# DAU_Kupplung_3phasig_V1_2.net
KiCad netlist of a schematic drawn in EAGLE
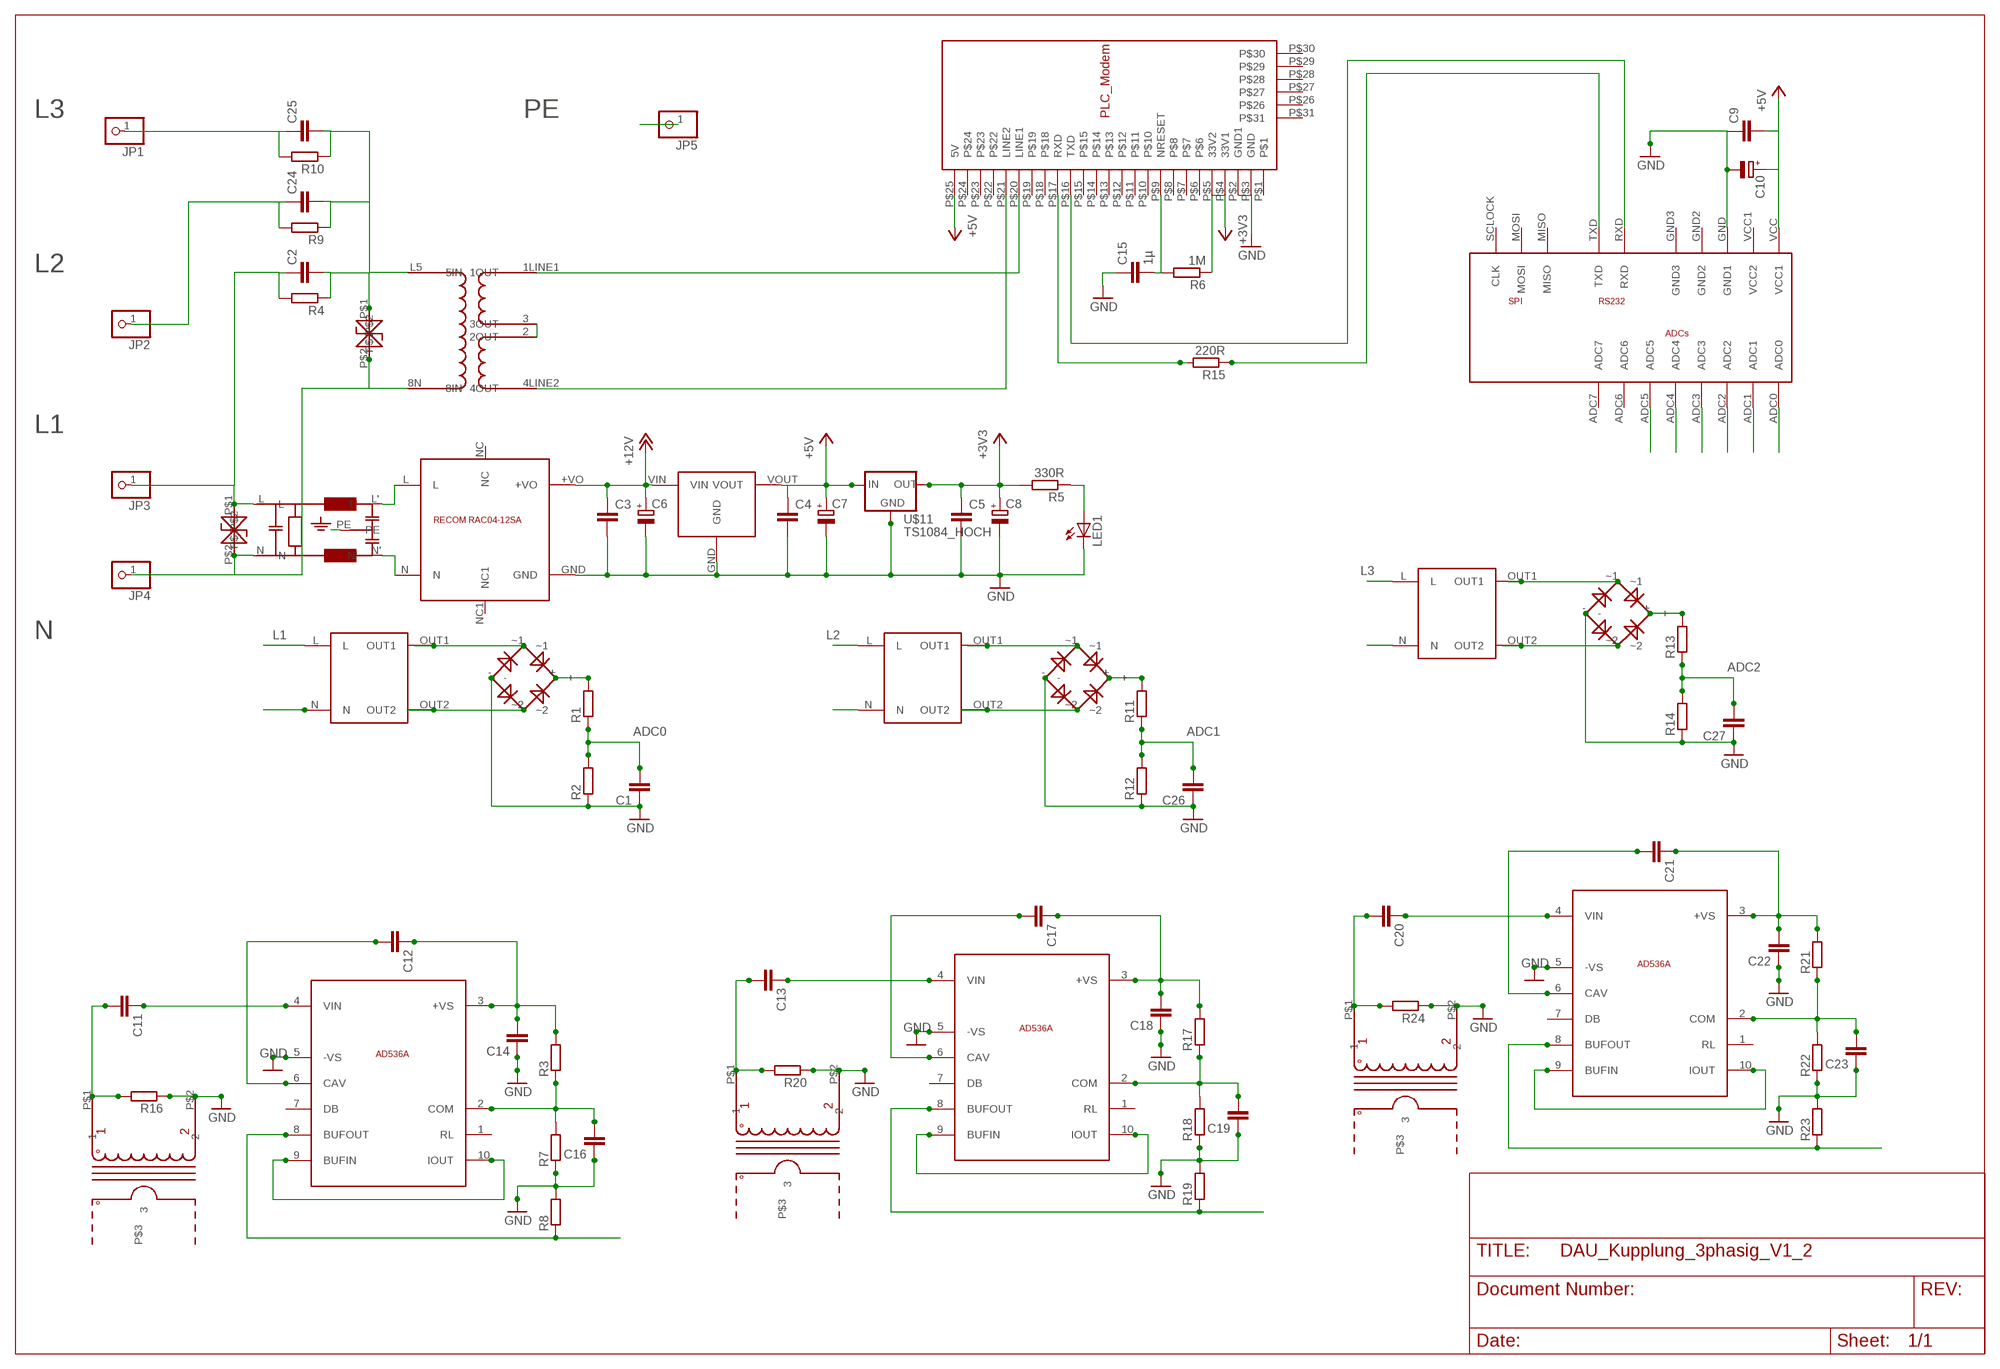
[diagram p0: schematic, sheet 1]

(export (version "E")
  (design (tool "Eeschema 10.0.6"))
  (components
    (comp (ref "C1")
      (value "C2,5-3")
      (footprint "eagle-import:C2.5-3")
      (libsource (lib "eagle-import") (part "C2,5-3"))
    )
    (comp (ref "C2")
      (value "C-EU225-087X268")
      (footprint "eagle-import:C225-087X268")
      (libsource (lib "eagle-import") (part "resistor_C-EU225-087X268"))
    )
    (comp (ref "C3")
      (value "C-EU025-040X050")
      (footprint "eagle-import:C025-040X050")
      (libsource (lib "eagle-import") (part "resistor_C-EU025-040X050"))
    )
    (comp (ref "C4")
      (value "C-EU025-040X050")
      (footprint "eagle-import:C025-040X050")
      (libsource (lib "eagle-import") (part "resistor_C-EU025-040X050"))
    )
    (comp (ref "C5")
      (value "C-EU025-040X050")
      (footprint "eagle-import:C025-040X050")
      (libsource (lib "eagle-import") (part "resistor_C-EU025-040X050"))
    )
    (comp (ref "C6")
      (value "CPOL-EUE2.5-6")
      (footprint "eagle-import:E2,5-6")
      (libsource (lib "eagle-import") (part "resistor_CPOL-EUE2.5-6"))
    )
    (comp (ref "C7")
      (value "CPOL-EUE2.5-6")
      (footprint "eagle-import:E2,5-6")
      (libsource (lib "eagle-import") (part "resistor_CPOL-EUE2.5-6"))
    )
    (comp (ref "C8")
      (value "CPOL-EUE2.5-6")
      (footprint "eagle-import:E2,5-6")
      (libsource (lib "eagle-import") (part "resistor_CPOL-EUE2.5-6"))
    )
    (comp (ref "C9")
      (value "C-EU025-040X050")
      (footprint "eagle-import:C025-040X050")
      (libsource (lib "eagle-import") (part "C-EU025-040X050"))
    )
    (comp (ref "C10")
      (value "CPOL-EUE2,5-6E")
      (footprint "eagle-import:E2,5-6E")
      (libsource (lib "eagle-import") (part "CPOL-EUE2,5-6E"))
    )
    (comp (ref "C11")
      (value "C2,5-3")
      (footprint "eagle-import:C2.5-3")
      (libsource (lib "eagle-import") (part "C2,5-3"))
    )
    (comp (ref "C12")
      (value "C2,5-3")
      (footprint "eagle-import:C2.5-3")
      (libsource (lib "eagle-import") (part "C2,5-3"))
    )
    (comp (ref "C13")
      (value "C2,5-3")
      (footprint "eagle-import:C2.5-3")
      (libsource (lib "eagle-import") (part "C2,5-3"))
    )
    (comp (ref "C14")
      (value "C2,5-3")
      (footprint "eagle-import:C2.5-3")
      (libsource (lib "eagle-import") (part "C2,5-3"))
    )
    (comp (ref "C15")
      (value "1µ")
      (footprint "eagle-import:C025-040X050")
      (libsource (lib "eagle-import") (part "resistor_C-EU025-040X050"))
    )
    (comp (ref "C16")
      (value "C2,5-3")
      (footprint "eagle-import:C2.5-3")
      (libsource (lib "eagle-import") (part "C2,5-3"))
    )
    (comp (ref "C17")
      (value "C2,5-3")
      (footprint "eagle-import:C2.5-3")
      (libsource (lib "eagle-import") (part "C2,5-3"))
    )
    (comp (ref "C18")
      (value "C2,5-3")
      (footprint "eagle-import:C2.5-3")
      (libsource (lib "eagle-import") (part "C2,5-3"))
    )
    (comp (ref "C19")
      (value "C2,5-3")
      (footprint "eagle-import:C2.5-3")
      (libsource (lib "eagle-import") (part "C2,5-3"))
    )
    (comp (ref "C20")
      (value "C2,5-3")
      (footprint "eagle-import:C2.5-3")
      (libsource (lib "eagle-import") (part "C2,5-3"))
    )
    (comp (ref "C21")
      (value "C2,5-3")
      (footprint "eagle-import:C2.5-3")
      (libsource (lib "eagle-import") (part "C2,5-3"))
    )
    (comp (ref "C22")
      (value "C2,5-3")
      (footprint "eagle-import:C2.5-3")
      (libsource (lib "eagle-import") (part "C2,5-3"))
    )
    (comp (ref "C23")
      (value "C2,5-3")
      (footprint "eagle-import:C2.5-3")
      (libsource (lib "eagle-import") (part "C2,5-3"))
    )
    (comp (ref "C24")
      (value "C-EU225-087X268")
      (footprint "eagle-import:C225-087X268")
      (libsource (lib "eagle-import") (part "resistor_C-EU225-087X268"))
    )
    (comp (ref "C25")
      (value "C-EU225-087X268")
      (footprint "eagle-import:C225-087X268")
      (libsource (lib "eagle-import") (part "resistor_C-EU225-087X268"))
    )
    (comp (ref "C26")
      (value "C2,5-3")
      (footprint "eagle-import:C2.5-3")
      (libsource (lib "eagle-import") (part "C2,5-3"))
    )
    (comp (ref "C27")
      (value "C2,5-3")
      (footprint "eagle-import:C2.5-3")
      (libsource (lib "eagle-import") (part "C2,5-3"))
    )
    (comp (ref "JP1")
      (value "PINHD-1X1")
      (footprint "eagle-import:1X01")
      (libsource (lib "eagle-import") (part "PINHD-1X1"))
    )
    (comp (ref "JP2")
      (value "PINHD-1X1")
      (footprint "eagle-import:1X01")
      (libsource (lib "eagle-import") (part "PINHD-1X1"))
    )
    (comp (ref "JP3")
      (value "PINHD-1X1")
      (footprint "eagle-import:1X01")
      (libsource (lib "eagle-import") (part "PINHD-1X1"))
    )
    (comp (ref "JP4")
      (value "PINHD-1X1")
      (footprint "eagle-import:1X01")
      (libsource (lib "eagle-import") (part "PINHD-1X1"))
    )
    (comp (ref "JP5")
      (value "PINHD-1X1")
      (footprint "eagle-import:1X01")
      (libsource (lib "eagle-import") (part "PINHD-1X1"))
    )
    (comp (ref "LED1")
      (value "LEDSQR2X5")
      (footprint "eagle-import:LED2X5")
      (libsource (lib "eagle-import") (part "LEDSQR2X5"))
    )
    (comp (ref "R1")
      (value "R-EU_0204/7")
      (footprint "eagle-import:0204_7")
      (libsource (lib "eagle-import") (part "R-EU_0204/7"))
    )
    (comp (ref "R2")
      (value "R-EU_0204/7")
      (footprint "eagle-import:0204_7")
      (libsource (lib "eagle-import") (part "R-EU_0204/7"))
    )
    (comp (ref "R3")
      (value "R-EU_0204/7")
      (footprint "eagle-import:0204_7")
      (libsource (lib "eagle-import") (part "R-EU_0204/7"))
    )
    (comp (ref "R4")
      (value "R-EU_0204/7")
      (footprint "eagle-import:0204_7")
      (libsource (lib "eagle-import") (part "R-EU_0204/7"))
    )
    (comp (ref "R5")
      (value "330R")
      (footprint "eagle-import:0204_7")
      (libsource (lib "eagle-import") (part "R-EU_0204/7"))
    )
    (comp (ref "R6")
      (value "1M")
      (footprint "eagle-import:0204_7")
      (libsource (lib "eagle-import") (part "R-EU_0204/7"))
    )
    (comp (ref "R7")
      (value "R-EU_0204/7")
      (footprint "eagle-import:0204_7")
      (libsource (lib "eagle-import") (part "R-EU_0204/7"))
    )
    (comp (ref "R8")
      (value "R-EU_0204/7")
      (footprint "eagle-import:0204_7")
      (libsource (lib "eagle-import") (part "R-EU_0204/7"))
    )
    (comp (ref "R9")
      (value "R-EU_0204/7")
      (footprint "eagle-import:0204_7")
      (libsource (lib "eagle-import") (part "R-EU_0204/7"))
    )
    (comp (ref "R10")
      (value "R-EU_0204/7")
      (footprint "eagle-import:0204_7")
      (libsource (lib "eagle-import") (part "R-EU_0204/7"))
    )
    (comp (ref "R11")
      (value "R-EU_0204/7")
      (footprint "eagle-import:0204_7")
      (libsource (lib "eagle-import") (part "R-EU_0204/7"))
    )
    (comp (ref "R12")
      (value "R-EU_0204/7")
      (footprint "eagle-import:0204_7")
      (libsource (lib "eagle-import") (part "R-EU_0204/7"))
    )
    (comp (ref "R13")
      (value "R-EU_0204/7")
      (footprint "eagle-import:0204_7")
      (libsource (lib "eagle-import") (part "R-EU_0204/7"))
    )
    (comp (ref "R14")
      (value "R-EU_0204/7")
      (footprint "eagle-import:0204_7")
      (libsource (lib "eagle-import") (part "R-EU_0204/7"))
    )
    (comp (ref "R15")
      (value "220R")
      (footprint "eagle-import:0204_7")
      (libsource (lib "eagle-import") (part "R-EU_0204/7"))
    )
    (comp (ref "R16")
      (value "R-EU_0204/7")
      (footprint "eagle-import:0204_7")
      (libsource (lib "eagle-import") (part "R-EU_0204/7"))
    )
    (comp (ref "R17")
      (value "R-EU_0204/7")
      (footprint "eagle-import:0204_7")
      (libsource (lib "eagle-import") (part "R-EU_0204/7"))
    )
    (comp (ref "R18")
      (value "R-EU_0204/7")
      (footprint "eagle-import:0204_7")
      (libsource (lib "eagle-import") (part "R-EU_0204/7"))
    )
    (comp (ref "R19")
      (value "R-EU_0204/7")
      (footprint "eagle-import:0204_7")
      (libsource (lib "eagle-import") (part "R-EU_0204/7"))
    )
    (comp (ref "R20")
      (value "R-EU_0204/7")
      (footprint "eagle-import:0204_7")
      (libsource (lib "eagle-import") (part "R-EU_0204/7"))
    )
    (comp (ref "R21")
      (value "R-EU_0204/7")
      (footprint "eagle-import:0204_7")
      (libsource (lib "eagle-import") (part "R-EU_0204/7"))
    )
    (comp (ref "R22")
      (value "R-EU_0204/7")
      (footprint "eagle-import:0204_7")
      (libsource (lib "eagle-import") (part "R-EU_0204/7"))
    )
    (comp (ref "R23")
      (value "R-EU_0204/7")
      (footprint "eagle-import:0204_7")
      (libsource (lib "eagle-import") (part "R-EU_0204/7"))
    )
    (comp (ref "R24")
      (value "R-EU_0204/7")
      (footprint "eagle-import:0204_7")
      (libsource (lib "eagle-import") (part "R-EU_0204/7"))
    )
    (comp (ref "TSV1")
      (value "TSV")
      (footprint "eagle-import:TSV")
      (libsource (lib "eagle-import") (part "TSV"))
    )
    (comp (ref "TSV2")
      (value "TSV")
      (footprint "eagle-import:TSV")
      (libsource (lib "eagle-import") (part "TSV"))
    )
    (comp (ref "U$1")
      (value "RECOM_RAC04_12SA")
      (footprint "eagle-import:RAC04_12SA")
      (libsource (lib "eagle-import") (part "RECOM_RAC04_12SA"))
    )
    (comp (ref "U$2")
      (value "SICHERHEITSTRAFO")
      (footprint "eagle-import:TRAFO_0,35VA")
      (libsource (lib "eagle-import") (part "SICHERHEITSTRAFO"))
    )
    (comp (ref "U$3")
      (value "ADUC831_MINIMUM")
      (footprint "eagle-import:ADUC_MINIMUM")
      (libsource (lib "eagle-import") (part "ADUC831_MINIMUM"))
    )
    (comp (ref "U$4")
      (value "MODEMSTECKER")
      (footprint "eagle-import:MODEM_FUSS")
      (libsource (lib "eagle-import") (part "MODEMSTECKER"))
    )
    (comp (ref "U$5")
      (value "PLC_UEBERTRAGER_V2")
      (footprint "eagle-import:PLC-UEBERTRAGER_V2")
      (libsource (lib "eagle-import") (part "PLC_UEBERTRAGER_V2"))
    )
    (comp (ref "U$6")
      (value "AC1010")
      (footprint "eagle-import:AC1010")
      (libsource (lib "eagle-import") (part "AC1010"))
    )
    (comp (ref "U$7")
      (value "AC1010")
      (footprint "eagle-import:AC1010")
      (libsource (lib "eagle-import") (part "AC1010"))
    )
    (comp (ref "U$8")
      (value "RECTIFIER")
      (footprint "eagle-import:RECTIFIER")
      (libsource (lib "eagle-import") (part "RECTIFIER"))
    )
    (comp (ref "U$10")
      (value "RECOM_785_05")
      (footprint "eagle-import:RECOM785X")
      (libsource (lib "eagle-import") (part "RECOM_785_05"))
    )
    (comp (ref "U$11")
      (value "TS1084_HOCH")
      (footprint "eagle-import:TS1084_HOCH")
      (libsource (lib "eagle-import") (part "TS1084_HOCH"))
    )
    (comp (ref "U$12")
      (value "AD536")
      (footprint "eagle-import:TO100_10PIN")
      (libsource (lib "eagle-import") (part "AD536"))
    )
    (comp (ref "U$13")
      (value "AD536")
      (footprint "eagle-import:TO100_10PIN")
      (libsource (lib "eagle-import") (part "AD536"))
    )
    (comp (ref "U$14")
      (value "AC1010")
      (footprint "eagle-import:AC1010")
      (libsource (lib "eagle-import") (part "AC1010"))
    )
    (comp (ref "U$15")
      (value "AD536")
      (footprint "eagle-import:TO100_10PIN")
      (libsource (lib "eagle-import") (part "AD536"))
    )
    (comp (ref "U$16")
      (value "SICHERHEITSTRAFO")
      (footprint "eagle-import:TRAFO_0,35VA")
      (libsource (lib "eagle-import") (part "SICHERHEITSTRAFO"))
    )
    (comp (ref "U$17")
      (value "RECTIFIER")
      (footprint "eagle-import:RECTIFIER")
      (libsource (lib "eagle-import") (part "RECTIFIER"))
    )
    (comp (ref "U$18")
      (value "SICHERHEITSTRAFO")
      (footprint "eagle-import:TRAFO_0,35VA")
      (libsource (lib "eagle-import") (part "SICHERHEITSTRAFO"))
    )
    (comp (ref "U$19")
      (value "RECTIFIER")
      (footprint "eagle-import:RECTIFIER")
      (libsource (lib "eagle-import") (part "RECTIFIER"))
    )
    (comp (ref "U$20")
      (value "NETZFILTER_05_A")
      (footprint "eagle-import:NETZFILTER")
      (libsource (lib "eagle-import") (part "NETZFILTER_05_A"))
    )
  )
  (nets
    (net (code "1") (name "+3V3") (class "Default")
      (node (ref "C5") (pin "1") (pinfunction "1_1") (pintype "passive"))
      (node (ref "C8") (pin "+") (pinfunction "+_+") (pintype "passive"))
      (node (ref "R5") (pin "2") (pinfunction "2_2") (pintype "passive"))
      (node (ref "R6") (pin "1") (pinfunction "1_1") (pintype "passive"))
      (node (ref "U$11") (pin "OUT") (pinfunction "OUT_OUT") (pintype "passive"))
      (node (ref "U$4") (pin "P$4") (pinfunction "33V1_P$4") (pintype "bidirectional"))
      (node (ref "U$4") (pin "P$5") (pinfunction "33V2_P$5") (pintype "bidirectional"))
    )
    (net (code "2") (name "+5V") (class "Default")
      (node (ref "C10") (pin "+") (pinfunction "+_+") (pintype "passive"))
      (node (ref "C4") (pin "1") (pinfunction "1_1") (pintype "passive"))
      (node (ref "C7") (pin "+") (pinfunction "+_+") (pintype "passive"))
      (node (ref "C9") (pin "2") (pinfunction "2_2") (pintype "passive"))
      (node (ref "U$10") (pin "VOUT") (pinfunction "VOUT_VOUT") (pintype "bidirectional"))
      (node (ref "U$11") (pin "IN") (pinfunction "IN_IN") (pintype "input"))
      (node (ref "U$3") (pin "VCC") (pinfunction "VCC1_VCC") (pintype "bidirectional"))
      (node (ref "U$4") (pin "P$25") (pinfunction "5V_P$25") (pintype "bidirectional"))
    )
    (net (code "3") (name "+12V") (class "Default")
      (node (ref "C3") (pin "1") (pinfunction "1_1") (pintype "passive"))
      (node (ref "C6") (pin "+") (pinfunction "+_+") (pintype "passive"))
      (node (ref "U$1") (pin "+VO") (pinfunction "+VO_+VO") (pintype "bidirectional"))
      (node (ref "U$10") (pin "VIN") (pinfunction "VIN_VIN") (pintype "bidirectional"))
    )
    (net (code "4") (name "/ADC0") (class "Default")
      (node (ref "C1") (pin "2") (pinfunction "2_2") (pintype "passive"))
      (node (ref "R1") (pin "1") (pinfunction "1_1") (pintype "passive"))
      (node (ref "R2") (pin "2") (pinfunction "2_2") (pintype "passive"))
      (node (ref "U$3") (pin "ADC0") (pinfunction "ADC0_ADC0") (pintype "bidirectional"))
    )
    (net (code "5") (name "/ADC1") (class "Default")
      (node (ref "C26") (pin "2") (pinfunction "2_2") (pintype "passive"))
      (node (ref "R11") (pin "1") (pinfunction "1_1") (pintype "passive"))
      (node (ref "R12") (pin "2") (pinfunction "2_2") (pintype "passive"))
      (node (ref "U$3") (pin "ADC1") (pinfunction "ADC1_ADC1") (pintype "bidirectional"))
    )
    (net (code "6") (name "/ADC2") (class "Default")
      (node (ref "C27") (pin "2") (pinfunction "2_2") (pintype "passive"))
      (node (ref "R13") (pin "1") (pinfunction "1_1") (pintype "passive"))
      (node (ref "R14") (pin "2") (pinfunction "2_2") (pintype "passive"))
      (node (ref "U$3") (pin "ADC2") (pinfunction "ADC2_ADC2") (pintype "bidirectional"))
    )
    (net (code "7") (name "/ADC3") (class "Default")
      (node (ref "R8") (pin "1") (pinfunction "1_1") (pintype "passive"))
      (node (ref "U$13") (pin "8") (pinfunction "BUFOUT_8") (pintype "bidirectional"))
      (node (ref "U$3") (pin "ADC3") (pinfunction "ADC3_ADC3") (pintype "bidirectional"))
    )
    (net (code "8") (name "/ADC4") (class "Default")
      (node (ref "R19") (pin "1") (pinfunction "1_1") (pintype "passive"))
      (node (ref "U$12") (pin "8") (pinfunction "BUFOUT_8") (pintype "bidirectional"))
      (node (ref "U$3") (pin "ADC4") (pinfunction "ADC4_ADC4") (pintype "bidirectional"))
    )
    (net (code "9") (name "/ADC5") (class "Default")
      (node (ref "R23") (pin "1") (pinfunction "1_1") (pintype "passive"))
      (node (ref "U$15") (pin "8") (pinfunction "BUFOUT_8") (pintype "bidirectional"))
      (node (ref "U$3") (pin "ADC5") (pinfunction "ADC5_ADC5") (pintype "bidirectional"))
    )
    (net (code "10") (name "/L1") (class "Default")
      (node (ref "C2") (pin "1") (pinfunction "1_1") (pintype "passive"))
      (node (ref "JP3") (pin "1") (pinfunction "1_1") (pintype "passive"))
      (node (ref "R4") (pin "2") (pinfunction "2_2") (pintype "passive"))
      (node (ref "TSV1") (pin "P$1") (pinfunction "P$1_P$1") (pintype "bidirectional"))
      (node (ref "U$2") (pin "L") (pinfunction "L_L") (pintype "bidirectional"))
      (node (ref "U$20") (pin "L") (pinfunction "L_L") (pintype "bidirectional"))
    )
    (net (code "11") (name "/L2") (class "Default")
      (node (ref "C24") (pin "1") (pinfunction "1_1") (pintype "passive"))
      (node (ref "JP2") (pin "1") (pinfunction "1_1") (pintype "passive"))
      (node (ref "R9") (pin "2") (pinfunction "2_2") (pintype "passive"))
      (node (ref "U$16") (pin "L") (pinfunction "L_L") (pintype "bidirectional"))
    )
    (net (code "12") (name "/L3") (class "Default")
      (node (ref "C25") (pin "1") (pinfunction "1_1") (pintype "passive"))
      (node (ref "JP1") (pin "1") (pinfunction "1_1") (pintype "passive"))
      (node (ref "R10") (pin "2") (pinfunction "2_2") (pintype "passive"))
      (node (ref "U$18") (pin "L") (pinfunction "L_L") (pintype "bidirectional"))
    )
    (net (code "13") (name "/N") (class "Default")
      (node (ref "JP4") (pin "1") (pinfunction "1_1") (pintype "passive"))
      (node (ref "TSV1") (pin "P$2") (pinfunction "P$2_P$2") (pintype "bidirectional"))
      (node (ref "TSV2") (pin "P$2") (pinfunction "P$2_P$2") (pintype "bidirectional"))
      (node (ref "U$16") (pin "N") (pinfunction "N_N") (pintype "bidirectional"))
      (node (ref "U$18") (pin "N") (pinfunction "N_N") (pintype "bidirectional"))
      (node (ref "U$2") (pin "N") (pinfunction "N_N") (pintype "bidirectional"))
      (node (ref "U$20") (pin "N") (pinfunction "N_N") (pintype "bidirectional"))
      (node (ref "U$5") (pin "8N") (pinfunction "8IN_8N") (pintype "input"))
    )
    (net (code "14") (name "/PE") (class "Default")
      (node (ref "JP5") (pin "1") (pinfunction "1_1") (pintype "passive"))
      (node (ref "U$20") (pin "PE") (pinfunction "PE_PE") (pintype "input"))
    )
    (net (code "15") (name "GND") (class "Default")
      (node (ref "C1") (pin "1") (pinfunction "1_1") (pintype "passive"))
      (node (ref "C10") (pin "-") (pinfunction "-_-") (pintype "passive"))
      (node (ref "C14") (pin "1") (pinfunction "1_1") (pintype "passive"))
      (node (ref "C15") (pin "1") (pinfunction "1_1") (pintype "passive"))
      (node (ref "C16") (pin "1") (pinfunction "1_1") (pintype "passive"))
      (node (ref "C18") (pin "1") (pinfunction "1_1") (pintype "passive"))
      (node (ref "C19") (pin "1") (pinfunction "1_1") (pintype "passive"))
      (node (ref "C22") (pin "1") (pinfunction "1_1") (pintype "passive"))
      (node (ref "C23") (pin "1") (pinfunction "1_1") (pintype "passive"))
      (node (ref "C26") (pin "1") (pinfunction "1_1") (pintype "passive"))
      (node (ref "C27") (pin "1") (pinfunction "1_1") (pintype "passive"))
      (node (ref "C3") (pin "2") (pinfunction "2_2") (pintype "passive"))
      (node (ref "C4") (pin "2") (pinfunction "2_2") (pintype "passive"))
      (node (ref "C5") (pin "2") (pinfunction "2_2") (pintype "passive"))
      (node (ref "C6") (pin "-") (pinfunction "-_-") (pintype "passive"))
      (node (ref "C7") (pin "-") (pinfunction "-_-") (pintype "passive"))
      (node (ref "C8") (pin "-") (pinfunction "-_-") (pintype "passive"))
      (node (ref "C9") (pin "1") (pinfunction "1_1") (pintype "passive"))
      (node (ref "LED1") (pin "K") (pinfunction "C_K") (pintype "passive"))
      (node (ref "R12") (pin "1") (pinfunction "1_1") (pintype "passive"))
      (node (ref "R14") (pin "1") (pinfunction "1_1") (pintype "passive"))
      (node (ref "R16") (pin "1") (pinfunction "1_1") (pintype "passive"))
      (node (ref "R18") (pin "1") (pinfunction "1_1") (pintype "passive"))
      (node (ref "R19") (pin "2") (pinfunction "2_2") (pintype "passive"))
      (node (ref "R2") (pin "1") (pinfunction "1_1") (pintype "passive"))
      (node (ref "R20") (pin "1") (pinfunction "1_1") (pintype "passive"))
      (node (ref "R22") (pin "1") (pinfunction "1_1") (pintype "passive"))
      (node (ref "R23") (pin "2") (pinfunction "2_2") (pintype "passive"))
      (node (ref "R24") (pin "1") (pinfunction "1_1") (pintype "passive"))
      (node (ref "R7") (pin "1") (pinfunction "1_1") (pintype "passive"))
      (node (ref "R8") (pin "2") (pinfunction "2_2") (pintype "passive"))
      (node (ref "U$1") (pin "GND") (pinfunction "GND_GND") (pintype "bidirectional"))
      (node (ref "U$10") (pin "GND") (pinfunction "GND_GND") (pintype "bidirectional"))
      (node (ref "U$11") (pin "GND") (pinfunction "GND_GND") (pintype "input"))
      (node (ref "U$12") (pin "5") (pinfunction "-VS_5") (pintype "bidirectional"))
      (node (ref "U$13") (pin "5") (pinfunction "-VS_5") (pintype "bidirectional"))
      (node (ref "U$14") (pin "P$2") (pinfunction "2_P$2") (pintype "output"))
      (node (ref "U$15") (pin "5") (pinfunction "-VS_5") (pintype "bidirectional"))
      (node (ref "U$17") (pin "-") (pinfunction "-_-") (pintype "bidirectional"))
      (node (ref "U$19") (pin "-") (pinfunction "-_-") (pintype "bidirectional"))
      (node (ref "U$3") (pin "GND") (pinfunction "GND1_GND") (pintype "bidirectional"))
      (node (ref "U$4") (pin "P$2") (pinfunction "GND1_P$2") (pintype "bidirectional"))
      (node (ref "U$4") (pin "P$3") (pinfunction "GND_P$3") (pintype "bidirectional"))
      (node (ref "U$6") (pin "P$2") (pinfunction "2_P$2") (pintype "output"))
      (node (ref "U$7") (pin "P$2") (pinfunction "2_P$2") (pintype "output"))
      (node (ref "U$8") (pin "-") (pinfunction "-_-") (pintype "bidirectional"))
    )
    (net (code "16") (name "Net-(LED1-PadA)") (class "Default")
      (node (ref "LED1") (pin "A") (pinfunction "A_A") (pintype "passive"))
      (node (ref "R5") (pin "1") (pinfunction "1_1") (pintype "passive"))
    )
    (net (code "17") (name "Net-(R1-Pad2)") (class "Default")
      (node (ref "R1") (pin "2") (pinfunction "2_2") (pintype "passive"))
      (node (ref "U$8") (pin "+") (pinfunction "+_+") (pintype "bidirectional"))
    )
    (net (code "18") (name "Net-(R11-Pad2)") (class "Default")
      (node (ref "R11") (pin "2") (pinfunction "2_2") (pintype "passive"))
      (node (ref "U$17") (pin "+") (pinfunction "+_+") (pintype "bidirectional"))
    )
    (net (code "19") (name "Net-(R13-Pad2)") (class "Default")
      (node (ref "R13") (pin "2") (pinfunction "2_2") (pintype "passive"))
      (node (ref "U$19") (pin "+") (pinfunction "+_+") (pintype "bidirectional"))
    )
    (net (code "20") (name "Net-(R15-Pad1)") (class "Default")
      (node (ref "R15") (pin "1") (pinfunction "1_1") (pintype "passive"))
      (node (ref "U$3") (pin "TXD") (pinfunction "TXD_TXD") (pintype "bidirectional"))
    )
    (net (code "21") (name "Net-(U$1-PadL)") (class "Default")
      (node (ref "U$1") (pin "L") (pinfunction "L_L") (pintype "bidirectional"))
      (node (ref "U$20") (pin "L'") (pinfunction "L'_L'") (pintype "bidirectional"))
    )
    (net (code "22") (name "Net-(U$1-PadN)") (class "Default")
      (node (ref "U$1") (pin "N") (pinfunction "N_N") (pintype "bidirectional"))
      (node (ref "U$20") (pin "N'") (pinfunction "N'_N'") (pintype "bidirectional"))
    )
    (net (code "23") (name "Net-(U$4-LINE1)") (class "Default")
      (node (ref "U$4") (pin "P$20") (pinfunction "LINE1_P$20") (pintype "bidirectional"))
      (node (ref "U$5") (pin "1LINE1") (pinfunction "1OUT_1LINE1") (pintype "output"))
    )
    (net (code "24") (name "Net-(U$4-LINE2)") (class "Default")
      (node (ref "U$4") (pin "P$21") (pinfunction "LINE2_P$21") (pintype "bidirectional"))
      (node (ref "U$5") (pin "4LINE2") (pinfunction "4OUT_4LINE2") (pintype "output"))
    )
    (net (code "25") (name "Net-(U$4-NRESET)") (class "Default")
      (node (ref "C15") (pin "2") (pinfunction "2_2") (pintype "passive"))
      (node (ref "R6") (pin "2") (pinfunction "2_2") (pintype "passive"))
      (node (ref "U$4") (pin "P$9") (pinfunction "NRESET_P$9") (pintype "bidirectional"))
    )
    (net (code "26") (name "Net-(U$4-RXD)") (class "Default")
      (node (ref "R15") (pin "2") (pinfunction "2_2") (pintype "passive"))
      (node (ref "U$4") (pin "P$17") (pinfunction "RXD_P$17") (pintype "bidirectional"))
    )
    (net (code "27") (name "Net-(U$4-TXD)") (class "Default")
      (node (ref "U$3") (pin "RXD") (pinfunction "RXD_RXD") (pintype "bidirectional"))
      (node (ref "U$4") (pin "P$16") (pinfunction "TXD_P$16") (pintype "bidirectional"))
    )
    (net (code "28") (name "Net-(U$5-2OUT)") (class "Default")
      (node (ref "U$5") (pin "2") (pinfunction "2OUT_2") (pintype "output"))
      (node (ref "U$5") (pin "3") (pinfunction "3OUT_3") (pintype "output"))
    )
    (net (code "29") (name "Net-(U$5-5IN)") (class "Default")
      (node (ref "C2") (pin "2") (pinfunction "2_2") (pintype "passive"))
      (node (ref "C24") (pin "2") (pinfunction "2_2") (pintype "passive"))
      (node (ref "C25") (pin "2") (pinfunction "2_2") (pintype "passive"))
      (node (ref "R10") (pin "1") (pinfunction "1_1") (pintype "passive"))
      (node (ref "R4") (pin "1") (pinfunction "1_1") (pintype "passive"))
      (node (ref "R9") (pin "1") (pinfunction "1_1") (pintype "passive"))
      (node (ref "TSV2") (pin "P$1") (pinfunction "P$1_P$1") (pintype "bidirectional"))
      (node (ref "U$5") (pin "L5") (pinfunction "5IN_L5") (pintype "input"))
    )
    (net (code "30") (name "Net-(U$6-1)") (class "Default")
      (node (ref "C11") (pin "2") (pinfunction "2_2") (pintype "passive"))
      (node (ref "R16") (pin "2") (pinfunction "2_2") (pintype "passive"))
      (node (ref "U$6") (pin "P$1") (pinfunction "1_P$1") (pintype "output"))
    )
    (net (code "31") (name "Net-(U$7-1)") (class "Default")
      (node (ref "C13") (pin "2") (pinfunction "2_2") (pintype "passive"))
      (node (ref "R20") (pin "2") (pinfunction "2_2") (pintype "passive"))
      (node (ref "U$7") (pin "P$1") (pinfunction "1_P$1") (pintype "output"))
    )
    (net (code "32") (name "Net-(U$8-~{1})") (class "Default")
      (node (ref "U$2") (pin "OUT1") (pinfunction "OUT1_OUT1") (pintype "bidirectional"))
      (node (ref "U$8") (pin "~1") (pinfunction "~{1}_~1") (pintype "bidirectional"))
    )
    (net (code "33") (name "Net-(U$8-~{2})") (class "Default")
      (node (ref "U$2") (pin "OUT2") (pinfunction "OUT2_OUT2") (pintype "bidirectional"))
      (node (ref "U$8") (pin "~2") (pinfunction "~{2}_~2") (pintype "bidirectional"))
    )
    (net (code "34") (name "Net-(U$12-+VS)") (class "Default")
      (node (ref "C17") (pin "1") (pinfunction "1_1") (pintype "passive"))
      (node (ref "C18") (pin "2") (pinfunction "2_2") (pintype "passive"))
      (node (ref "R17") (pin "2") (pinfunction "2_2") (pintype "passive"))
      (node (ref "U$12") (pin "3") (pinfunction "+VS_3") (pintype "bidirectional"))
    )
    (net (code "35") (name "Net-(U$12-BUFIN)") (class "Default")
      (node (ref "U$12") (pin "10") (pinfunction "IOUT_10") (pintype "bidirectional"))
      (node (ref "U$12") (pin "9") (pinfunction "BUFIN_9") (pintype "bidirectional"))
    )
    (net (code "36") (name "Net-(U$12-CAV)") (class "Default")
      (node (ref "C17") (pin "2") (pinfunction "2_2") (pintype "passive"))
      (node (ref "U$12") (pin "6") (pinfunction "CAV_6") (pintype "bidirectional"))
    )
    (net (code "37") (name "Net-(U$12-COM)") (class "Default")
      (node (ref "C19") (pin "2") (pinfunction "2_2") (pintype "passive"))
      (node (ref "R17") (pin "1") (pinfunction "1_1") (pintype "passive"))
      (node (ref "R18") (pin "2") (pinfunction "2_2") (pintype "passive"))
      (node (ref "U$12") (pin "2") (pinfunction "COM_2") (pintype "bidirectional"))
    )
    (net (code "38") (name "Net-(U$12-VIN)") (class "Default")
      (node (ref "C13") (pin "1") (pinfunction "1_1") (pintype "passive"))
      (node (ref "U$12") (pin "4") (pinfunction "VIN_4") (pintype "bidirectional"))
    )
    (net (code "39") (name "Net-(U$13-+VS)") (class "Default")
      (node (ref "C12") (pin "1") (pinfunction "1_1") (pintype "passive"))
      (node (ref "C14") (pin "2") (pinfunction "2_2") (pintype "passive"))
      (node (ref "R3") (pin "2") (pinfunction "2_2") (pintype "passive"))
      (node (ref "U$13") (pin "3") (pinfunction "+VS_3") (pintype "bidirectional"))
    )
    (net (code "40") (name "Net-(U$13-BUFIN)") (class "Default")
      (node (ref "U$13") (pin "10") (pinfunction "IOUT_10") (pintype "bidirectional"))
      (node (ref "U$13") (pin "9") (pinfunction "BUFIN_9") (pintype "bidirectional"))
    )
    (net (code "41") (name "Net-(U$13-CAV)") (class "Default")
      (node (ref "C12") (pin "2") (pinfunction "2_2") (pintype "passive"))
      (node (ref "U$13") (pin "6") (pinfunction "CAV_6") (pintype "bidirectional"))
    )
    (net (code "42") (name "Net-(U$13-COM)") (class "Default")
      (node (ref "C16") (pin "2") (pinfunction "2_2") (pintype "passive"))
      (node (ref "R3") (pin "1") (pinfunction "1_1") (pintype "passive"))
      (node (ref "R7") (pin "2") (pinfunction "2_2") (pintype "passive"))
      (node (ref "U$13") (pin "2") (pinfunction "COM_2") (pintype "bidirectional"))
    )
    (net (code "43") (name "Net-(U$13-VIN)") (class "Default")
      (node (ref "C11") (pin "1") (pinfunction "1_1") (pintype "passive"))
      (node (ref "U$13") (pin "4") (pinfunction "VIN_4") (pintype "bidirectional"))
    )
    (net (code "44") (name "Net-(U$14-1)") (class "Default")
      (node (ref "C20") (pin "2") (pinfunction "2_2") (pintype "passive"))
      (node (ref "R24") (pin "2") (pinfunction "2_2") (pintype "passive"))
      (node (ref "U$14") (pin "P$1") (pinfunction "1_P$1") (pintype "output"))
    )
    (net (code "45") (name "Net-(U$15-+VS)") (class "Default")
      (node (ref "C21") (pin "1") (pinfunction "1_1") (pintype "passive"))
      (node (ref "C22") (pin "2") (pinfunction "2_2") (pintype "passive"))
      (node (ref "R21") (pin "2") (pinfunction "2_2") (pintype "passive"))
      (node (ref "U$15") (pin "3") (pinfunction "+VS_3") (pintype "bidirectional"))
    )
    (net (code "46") (name "Net-(U$15-BUFIN)") (class "Default")
      (node (ref "U$15") (pin "10") (pinfunction "IOUT_10") (pintype "bidirectional"))
      (node (ref "U$15") (pin "9") (pinfunction "BUFIN_9") (pintype "bidirectional"))
    )
    (net (code "47") (name "Net-(U$15-CAV)") (class "Default")
      (node (ref "C21") (pin "2") (pinfunction "2_2") (pintype "passive"))
      (node (ref "U$15") (pin "6") (pinfunction "CAV_6") (pintype "bidirectional"))
    )
    (net (code "48") (name "Net-(U$15-COM)") (class "Default")
      (node (ref "C23") (pin "2") (pinfunction "2_2") (pintype "passive"))
      (node (ref "R21") (pin "1") (pinfunction "1_1") (pintype "passive"))
      (node (ref "R22") (pin "2") (pinfunction "2_2") (pintype "passive"))
      (node (ref "U$15") (pin "2") (pinfunction "COM_2") (pintype "bidirectional"))
    )
    (net (code "49") (name "Net-(U$15-VIN)") (class "Default")
      (node (ref "C20") (pin "1") (pinfunction "1_1") (pintype "passive"))
      (node (ref "U$15") (pin "4") (pinfunction "VIN_4") (pintype "bidirectional"))
    )
    (net (code "50") (name "Net-(U$17-~{1})") (class "Default")
      (node (ref "U$16") (pin "OUT1") (pinfunction "OUT1_OUT1") (pintype "bidirectional"))
      (node (ref "U$17") (pin "~1") (pinfunction "~{1}_~1") (pintype "bidirectional"))
    )
    (net (code "51") (name "Net-(U$17-~{2})") (class "Default")
      (node (ref "U$16") (pin "OUT2") (pinfunction "OUT2_OUT2") (pintype "bidirectional"))
      (node (ref "U$17") (pin "~2") (pinfunction "~{2}_~2") (pintype "bidirectional"))
    )
    (net (code "52") (name "Net-(U$19-~{1})") (class "Default")
      (node (ref "U$18") (pin "OUT1") (pinfunction "OUT1_OUT1") (pintype "bidirectional"))
      (node (ref "U$19") (pin "~1") (pinfunction "~{1}_~1") (pintype "bidirectional"))
    )
    (net (code "53") (name "Net-(U$19-~{2})") (class "Default")
      (node (ref "U$18") (pin "OUT2") (pinfunction "OUT2_OUT2") (pintype "bidirectional"))
      (node (ref "U$19") (pin "~2") (pinfunction "~{2}_~2") (pintype "bidirectional"))
    )
    (net (code "54") (name "unconnected-(U$1-PadNC)") (class "Default")
      (node (ref "U$1") (pin "NC") (pinfunction "NC_NC") (pintype "bidirectional"))
    )
    (net (code "55") (name "unconnected-(U$1-PadNC1)") (class "Default")
      (node (ref "U$1") (pin "NC1") (pinfunction "NC1_NC1") (pintype "bidirectional"))
    )
    (net (code "56") (name "unconnected-(U$3-CLK-PadSCLOCK)") (class "Default")
      (node (ref "U$3") (pin "SCLOCK") (pinfunction "CLK_SCLOCK") (pintype "bidirectional"))
    )
    (net (code "57") (name "unconnected-(U$3-PadADC6)") (class "Default")
      (node (ref "U$3") (pin "ADC6") (pinfunction "ADC6_ADC6") (pintype "bidirectional"))
    )
    (net (code "58") (name "unconnected-(U$3-PadADC7)") (class "Default")
      (node (ref "U$3") (pin "ADC7") (pinfunction "ADC7_ADC7") (pintype "bidirectional"))
    )
    (net (code "59") (name "unconnected-(U$3-PadGND2)") (class "Default")
      (node (ref "U$3") (pin "GND2") (pinfunction "GND2_GND2") (pintype "bidirectional"))
    )
    (net (code "60") (name "unconnected-(U$3-PadGND3)") (class "Default")
      (node (ref "U$3") (pin "GND3") (pinfunction "GND3_GND3") (pintype "bidirectional"))
    )
    (net (code "61") (name "unconnected-(U$3-PadMISO)") (class "Default")
      (node (ref "U$3") (pin "MISO") (pinfunction "MISO_MISO") (pintype "bidirectional"))
    )
    (net (code "62") (name "unconnected-(U$3-PadMOSI)") (class "Default")
      (node (ref "U$3") (pin "MOSI") (pinfunction "MOSI_MOSI") (pintype "bidirectional"))
    )
    (net (code "63") (name "unconnected-(U$3-VCC2-PadVCC1)") (class "Default")
      (node (ref "U$3") (pin "VCC1") (pinfunction "VCC2_VCC1") (pintype "bidirectional"))
    )
    (net (code "64") (name "unconnected-(U$4-PadP$1)") (class "Default")
      (node (ref "U$4") (pin "P$1") (pinfunction "P$1_P$1") (pintype "bidirectional"))
    )
    (net (code "65") (name "unconnected-(U$4-PadP$6)") (class "Default")
      (node (ref "U$4") (pin "P$6") (pinfunction "P$6_P$6") (pintype "bidirectional"))
    )
    (net (code "66") (name "unconnected-(U$4-PadP$7)") (class "Default")
      (node (ref "U$4") (pin "P$7") (pinfunction "P$7_P$7") (pintype "bidirectional"))
    )
    (net (code "67") (name "unconnected-(U$4-PadP$8)") (class "Default")
      (node (ref "U$4") (pin "P$8") (pinfunction "P$8_P$8") (pintype "bidirectional"))
    )
    (net (code "68") (name "unconnected-(U$4-PadP$10)") (class "Default")
      (node (ref "U$4") (pin "P$10") (pinfunction "P$10_P$10") (pintype "bidirectional"))
    )
    (net (code "69") (name "unconnected-(U$4-PadP$11)") (class "Default")
      (node (ref "U$4") (pin "P$11") (pinfunction "P$11_P$11") (pintype "bidirectional"))
    )
    (net (code "70") (name "unconnected-(U$4-PadP$12)") (class "Default")
      (node (ref "U$4") (pin "P$12") (pinfunction "P$12_P$12") (pintype "bidirectional"))
    )
    (net (code "71") (name "unconnected-(U$4-PadP$13)") (class "Default")
      (node (ref "U$4") (pin "P$13") (pinfunction "P$13_P$13") (pintype "bidirectional"))
    )
    (net (code "72") (name "unconnected-(U$4-PadP$14)") (class "Default")
      (node (ref "U$4") (pin "P$14") (pinfunction "P$14_P$14") (pintype "bidirectional"))
    )
    (net (code "73") (name "unconnected-(U$4-PadP$15)") (class "Default")
      (node (ref "U$4") (pin "P$15") (pinfunction "P$15_P$15") (pintype "bidirectional"))
    )
    (net (code "74") (name "unconnected-(U$4-PadP$18)") (class "Default")
      (node (ref "U$4") (pin "P$18") (pinfunction "P$18_P$18") (pintype "bidirectional"))
    )
    (net (code "75") (name "unconnected-(U$4-PadP$19)") (class "Default")
      (node (ref "U$4") (pin "P$19") (pinfunction "P$19_P$19") (pintype "bidirectional"))
    )
    (net (code "76") (name "unconnected-(U$4-PadP$22)") (class "Default")
      (node (ref "U$4") (pin "P$22") (pinfunction "P$22_P$22") (pintype "bidirectional"))
    )
    (net (code "77") (name "unconnected-(U$4-PadP$23)") (class "Default")
      (node (ref "U$4") (pin "P$23") (pinfunction "P$23_P$23") (pintype "bidirectional"))
    )
    (net (code "78") (name "unconnected-(U$4-PadP$24)") (class "Default")
      (node (ref "U$4") (pin "P$24") (pinfunction "P$24_P$24") (pintype "bidirectional"))
    )
    (net (code "79") (name "unconnected-(U$4-PadP$26)") (class "Default")
      (node (ref "U$4") (pin "P$26") (pinfunction "P$26_P$26") (pintype "bidirectional"))
    )
    (net (code "80") (name "unconnected-(U$4-PadP$27)") (class "Default")
      (node (ref "U$4") (pin "P$27") (pinfunction "P$27_P$27") (pintype "bidirectional"))
    )
    (net (code "81") (name "unconnected-(U$4-PadP$28)") (class "Default")
      (node (ref "U$4") (pin "P$28") (pinfunction "P$28_P$28") (pintype "bidirectional"))
    )
    (net (code "82") (name "unconnected-(U$4-PadP$29)") (class "Default")
      (node (ref "U$4") (pin "P$29") (pinfunction "P$29_P$29") (pintype "bidirectional"))
    )
    (net (code "83") (name "unconnected-(U$4-PadP$30)") (class "Default")
      (node (ref "U$4") (pin "P$30") (pinfunction "P$30_P$30") (pintype "bidirectional"))
    )
    (net (code "84") (name "unconnected-(U$4-PadP$31)") (class "Default")
      (node (ref "U$4") (pin "P$31") (pinfunction "P$31_P$31") (pintype "bidirectional"))
    )
    (net (code "85") (name "unconnected-(U$6-3-PadP$3)") (class "Default")
      (node (ref "U$6") (pin "P$3") (pinfunction "3_P$3") (pintype "no_connect"))
    )
    (net (code "86") (name "unconnected-(U$7-3-PadP$3)") (class "Default")
      (node (ref "U$7") (pin "P$3") (pinfunction "3_P$3") (pintype "no_connect"))
    )
    (net (code "87") (name "unconnected-(U$12-DB-Pad7)") (class "Default")
      (node (ref "U$12") (pin "7") (pinfunction "DB_7") (pintype "bidirectional"))
    )
    (net (code "88") (name "unconnected-(U$12-RL-Pad1)") (class "Default")
      (node (ref "U$12") (pin "1") (pinfunction "RL_1") (pintype "bidirectional"))
    )
    (net (code "89") (name "unconnected-(U$13-DB-Pad7)") (class "Default")
      (node (ref "U$13") (pin "7") (pinfunction "DB_7") (pintype "bidirectional"))
    )
    (net (code "90") (name "unconnected-(U$13-RL-Pad1)") (class "Default")
      (node (ref "U$13") (pin "1") (pinfunction "RL_1") (pintype "bidirectional"))
    )
    (net (code "91") (name "unconnected-(U$14-3-PadP$3)") (class "Default")
      (node (ref "U$14") (pin "P$3") (pinfunction "3_P$3") (pintype "no_connect"))
    )
    (net (code "92") (name "unconnected-(U$15-DB-Pad7)") (class "Default")
      (node (ref "U$15") (pin "7") (pinfunction "DB_7") (pintype "bidirectional"))
    )
    (net (code "93") (name "unconnected-(U$15-RL-Pad1)") (class "Default")
      (node (ref "U$15") (pin "1") (pinfunction "RL_1") (pintype "bidirectional"))
    )
  )
)
